# Top.net
KiCad netlist of a schematic drawn in Altium Designer
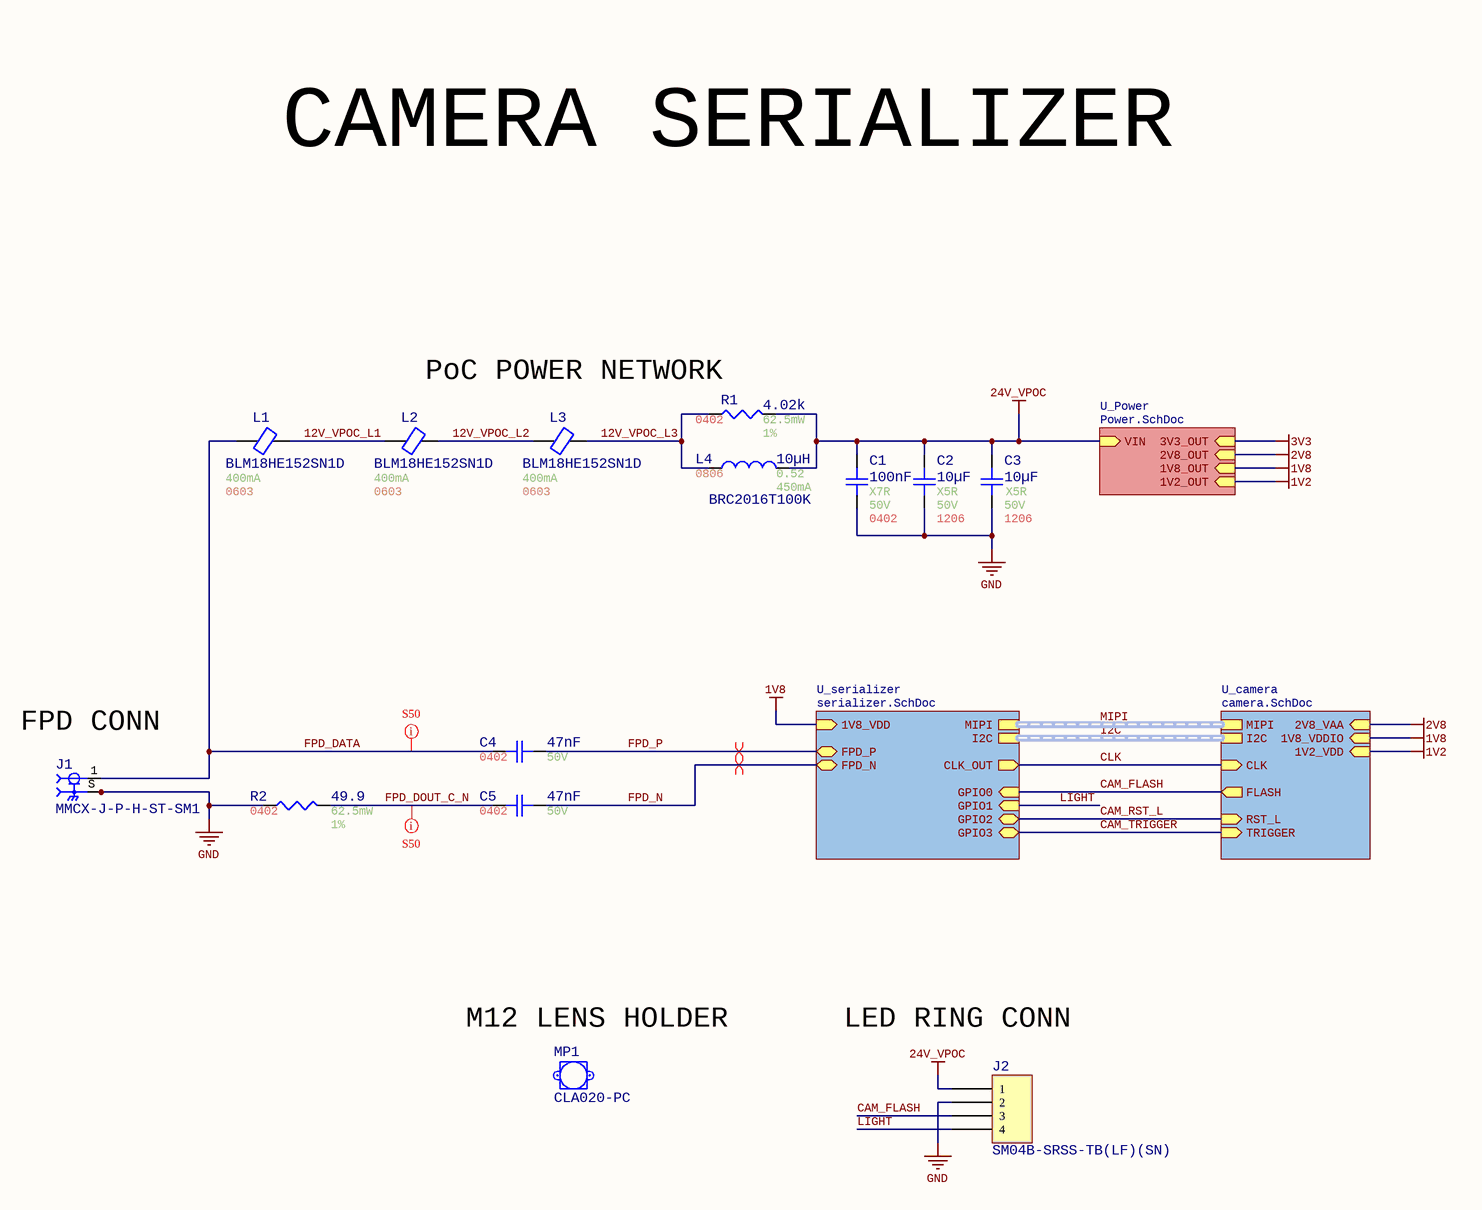
[diagram p0: Top.SchDoc]

(export (version "E")
  (design (tool "Eeschema 10.0.6"))
  (components
    (comp (ref "C1")
      (value "100nF")
      (footprint "Generic 0402 capacitor")
      (fields
        (field (name "TEMPERATURE COEFFICIENT") "X7R")
        (field (name "VOLTAGE RATING") "50V")
        (field (name "CASE/PACKAGE") "0402")
        (field (name "TOLERANCE") "10%")
        (field (name "Comment") "GRT155R71H104KE01D")
      )
      (libsource (lib "Raise Robotics") (part "Unpolarized Capacitor"))
    )
    (comp (ref "C2")
      (value "10µF")
      (footprint "Generic 1206 Capacitor")
      (fields
        (field (name "TEMPERATURE COEFFICIENT") "X5R")
        (field (name "VOLTAGE RATING") "50V")
        (field (name "CASE/PACKAGE") "1206")
        (field (name "TOLERANCE") "20%")
        (field (name "Comment") "CL31A106MBHNNNE")
      )
      (libsource (lib "Raise Robotics") (part "Unpolarized Capacitor"))
    )
    (comp (ref "C3")
      (value "10µF")
      (footprint "Generic 1206 Capacitor")
      (fields
        (field (name "TEMPERATURE COEFFICIENT") "X5R")
        (field (name "VOLTAGE RATING") "50V")
        (field (name "CASE/PACKAGE") "1206")
        (field (name "TOLERANCE") "20%")
        (field (name "Comment") "CL31A106MBHNNNE")
      )
      (libsource (lib "Raise Robotics") (part "Unpolarized Capacitor"))
    )
    (comp (ref "C4")
      (value "47nF")
      (footprint "Generic 0402 capacitor")
      (description "50V 47nF X7R ±10% 0402 Multilayer Ceramic Capacitors MLCC - SMD/SMT ROHS")
      (fields
        (field (name "VOLTAGE RATING") "50V")
        (field (name "CASE/PACKAGE") "0402")
        (field (name "TOLERANCE") "10%")
        (field (name "Comment") "GRM155R71H473KE14D")
      )
      (libsource (lib "Raise Robotics") (part "Unpolarized Capacitor"))
    )
    (comp (ref "C5")
      (value "47nF")
      (footprint "Generic 0402 capacitor")
      (description "50V 47nF X7R ±10% 0402 Multilayer Ceramic Capacitors MLCC - SMD/SMT ROHS")
      (fields
        (field (name "VOLTAGE RATING") "50V")
        (field (name "CASE/PACKAGE") "0402")
        (field (name "TOLERANCE") "10%")
        (field (name "Comment") "GRM155R71H473KE14D")
      )
      (libsource (lib "Raise Robotics") (part "Unpolarized Capacitor"))
    )
    (comp (ref "J1")
      (value "MMCX-J-P-H-ST-SM1")
      (footprint "MMCX-J-P-H-ST-SM1")
      (description "RF / Coaxial Connector, MMCX Coaxial, Straight Jack, Surface Mount Vertical, 50 ohm")
      (fields (field (name "MANUFACTURER") "Samtec"))
      (libsource (lib "Raise Robotics") (part "RF 1pin + 4 shield"))
    )
    (comp (ref "J2")
      (value "SM04B-SRSS-TB(LF)(SN)")
      (footprint "JST SM04B-SRSS-TB")
      (description "CONN HEADER SMD R/A 4POS 1MM")
      (fields (field (name "MANUFACTURER") "JST Sales America Inc."))
      (libsource (lib "Celestial Altium Library - altium_library") (part "4 Pin"))
    )
    (comp (ref "L1")
      (value "BLM18HE152SN1D")
      (footprint "0603_1.6x0.8x0.8mm_IND")
      (description "Ferrite Beads Multi-Layer 1.5KOhm 25% 100MHz 500mA 500mOhm DCR 0603 T/R")
      (fields
        (field (name "CURRENT RATING") "400mA")
        (field (name "CASE/PACKAGE") "0603")
        (field (name "TOLERANCE") "25%")
      )
      (libsource (lib "Raise Robotics") (part "Generic 2 pin ferrite bead"))
    )
    (comp (ref "L2")
      (value "BLM18HE152SN1D")
      (footprint "0603_1.6x0.8x0.8mm_IND")
      (description "Ferrite Beads Multi-Layer 1.5KOhm 25% 100MHz 500mA 500mOhm DCR 0603 T/R")
      (fields
        (field (name "CURRENT RATING") "400mA")
        (field (name "CASE/PACKAGE") "0603")
        (field (name "TOLERANCE") "25%")
      )
      (libsource (lib "Raise Robotics") (part "Generic 2 pin ferrite bead"))
    )
    (comp (ref "L3")
      (value "BLM18HE152SN1D")
      (footprint "0603_1.6x0.8x0.8mm_IND")
      (description "Ferrite Beads Multi-Layer 1.5KOhm 25% 100MHz 500mA 500mOhm DCR 0603 T/R")
      (fields
        (field (name "CURRENT RATING") "400mA")
        (field (name "CASE/PACKAGE") "0603")
        (field (name "TOLERANCE") "25%")
      )
      (libsource (lib "Raise Robotics") (part "Generic 2 pin ferrite bead"))
    )
    (comp (ref "L4")
      (value "BRC2016T100K")
      (footprint "0805_2.0x1.6x1.6mm_IND")
      (description "IND 10UH 20% 3.1A SHD")
      (fields
        (field (name "DCR") "0.52")
        (field (name "CURRENT RATING") "450mA")
        (field (name "CASE/PACKAGE") "0806")
        (field (name "ALTIUM_VALUE") "10µH")
        (field (name "TOLERANCE") "10%")
      )
      (libsource (lib "Raise Robotics") (part "Generic 2 pin inductor"))
    )
    (comp (ref "MP1")
      (value "CLA020-PC")
      (footprint "M12_lens_holder_20mm")
      (description "M12 camera lens holder - 20mm spacing")
      (libsource (lib "Raise Robotics") (part "PT-LH008P-Symbol-1"))
    )
    (comp (ref "R1")
      (value "4.02k")
      (footprint "Generic 0402 Resistor")
      (description "Fixed Resistor, Metal Glaze/Thick Film, 0.063W, 4020ohm, 50V, 1% +/-Tol, Surface Mount, 0402")
      (fields
        (field (name "POWER") "62.5mW")
        (field (name "TOLERANCE") "1%")
        (field (name "CASE/PACKAGE") "0402")
        (field (name "MANUFACTURER PART NUMBER") "Blank")
        (field (name "Comment") "RCA04024K02FKEDSR")
      )
      (libsource (lib "Raise Robotics") (part "Resistor"))
    )
    (comp (ref "R2")
      (value "49.9")
      (footprint "Generic 0402 Resistor")
      (description "RES, 0402, 49.9 ohm, 1%, 0.1W, AUTO")
      (fields
        (field (name "POWER") "62.5mW")
        (field (name "TOLERANCE") "1%")
        (field (name "CASE/PACKAGE") "0402")
        (field (name "MANUFACTURER PART NUMBER") "RMCA0402FT49R9-HP")
      )
      (libsource (lib "Raise Robotics") (part "Resistor"))
    )
  )
  (nets
    (net (code "3") (name "/12V_VPOC_L1") (class "Default")
      (node (ref "L1") (pin "2") (pinfunction "2_2") (pintype "passive"))
      (node (ref "L2") (pin "1") (pinfunction "1_1") (pintype "passive"))
    )
    (net (code "4") (name "/12V_VPOC_L2") (class "Default")
      (node (ref "L2") (pin "2") (pinfunction "2_2") (pintype "passive"))
      (node (ref "L3") (pin "1") (pinfunction "1_1") (pintype "passive"))
    )
    (net (code "5") (name "/12V_VPOC_L3") (class "Default")
      (node (ref "L3") (pin "2") (pinfunction "2_2") (pintype "passive"))
      (node (ref "L4") (pin "1") (pinfunction "1_1") (pintype "passive"))
      (node (ref "R1") (pin "1") (pinfunction "1_1") (pintype "passive"))
    )
    (net (code "6") (name "/CAM_FLASH") (class "Default")
      (node (ref "J2") (pin "3") (pinfunction "3_3") (pintype "passive"))
    )
    (net (code "10") (name "/FPD_DATA") (class "Default")
      (node (ref "C4") (pin "2") (pinfunction "2_2") (pintype "passive"))
      (node (ref "J1") (pin "1") (pinfunction "1_1") (pintype "passive"))
      (node (ref "L1") (pin "1") (pinfunction "1_1") (pintype "passive"))
    )
    (net (code "11") (name "/FPD_DOUT_C_N") (class "Default")
      (node (ref "C5") (pin "2") (pinfunction "2_2") (pintype "passive"))
      (node (ref "R2") (pin "2") (pinfunction "2_2") (pintype "passive"))
    )
    (net (code "12") (name "/FPD_N") (class "Default")
      (node (ref "C5") (pin "1") (pinfunction "1_1") (pintype "passive"))
    )
    (net (code "13") (name "/FPD_P") (class "Default")
      (node (ref "C4") (pin "1") (pinfunction "1_1") (pintype "passive"))
    )
    (net (code "14") (name "/LIGHT") (class "Default")
      (node (ref "J2") (pin "4") (pinfunction "4_4") (pintype "passive"))
    )
    (net (code "21") (name "24V_VPOC") (class "Default")
      (node (ref "C1") (pin "2") (pinfunction "2_2") (pintype "passive"))
      (node (ref "C2") (pin "2") (pinfunction "2_2") (pintype "passive"))
      (node (ref "C3") (pin "2") (pinfunction "2_2") (pintype "passive"))
      (node (ref "J2") (pin "1") (pinfunction "1_1") (pintype "passive"))
      (node (ref "L4") (pin "2") (pinfunction "2_2") (pintype "passive"))
      (node (ref "R1") (pin "2") (pinfunction "2_2") (pintype "passive"))
    )
    (net (code "22") (name "GND") (class "Default")
      (node (ref "C1") (pin "1") (pinfunction "1_1") (pintype "passive"))
      (node (ref "C2") (pin "1") (pinfunction "1_1") (pintype "passive"))
      (node (ref "C3") (pin "1") (pinfunction "1_1") (pintype "passive"))
      (node (ref "J1") (pin "S1") (pinfunction "2_S1") (pintype "passive"))
      (node (ref "J1") (pin "S2") (pinfunction "2_S2") (pintype "passive"))
      (node (ref "J1") (pin "S3") (pinfunction "2_S3") (pintype "passive"))
      (node (ref "J1") (pin "S4") (pinfunction "2_S4") (pintype "passive"))
      (node (ref "J2") (pin "2") (pinfunction "2_2") (pintype "passive"))
      (node (ref "R2") (pin "1") (pinfunction "1_1") (pintype "passive"))
    )
  )
)
